# UCAGPS.net
KiCad netlist of a schematic drawn in Altium Designer
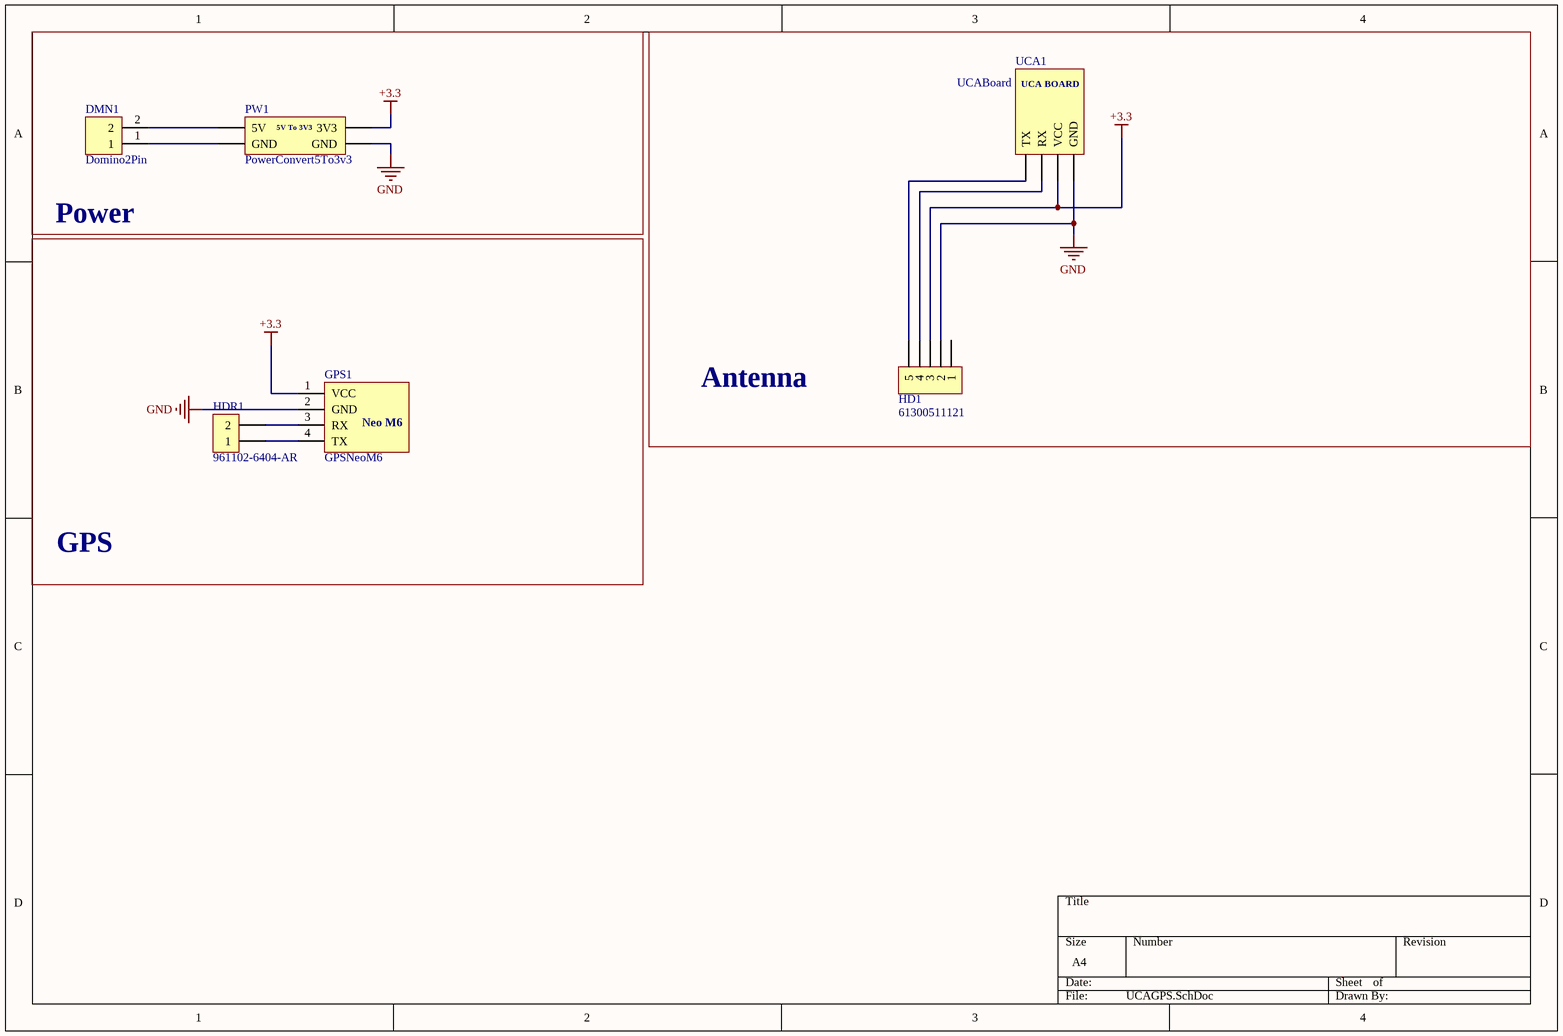
[diagram p0: UCAGPS.SchDoc]

(export (version "E")
  (design (tool "Eeschema 10.0.6"))
  (components
    (comp (ref "DMN1")
      (value "Domino2Pin")
      (footprint "CONN-SIL2")
      (libsource (lib "UCAGPS") (part "Domino2Pin"))
    )
    (comp (ref "GPS1") (value "GPSNeoM6") (footprint "GPSNEOM6") (libsource (lib "UCAGPS") (part "GPSNeoM6")))
    (comp (ref "HD1")
      (value "61300511121")
      (footprint "HEADER")
      (fields (field (name "MANUFACTURER") "Wurth Electronics"))
      (libsource (lib "UCAGPS") (part "61300511121"))
    )
    (comp (ref "HDR1")
      (value "961102-6404-AR")
      (footprint "header2pin")
      (description "CONN HEADER VERT SGL 2POS GOLD")
      (fields (field (name "MANUFACTURER") "3M"))
      (libsource (lib "UCAGPS") (part "961102-6404-AR"))
    )
    (comp (ref "PW1")
      (value "PowerConvert5To3v3")
      (footprint "PowerConvert5To3v3")
      (description "Convert 5 to 3.3")
      (libsource (lib "UCAGPS") (part "PowerConvert5To3v3"))
    )
    (comp (ref "UCA1") (value "UCABoard") (footprint "UCABOARD") (libsource (lib "UCAGPS") (part "UCABoard")))
  )
  (nets
    (net (code "1") (name "+3.3") (class "Default")
      (node (ref "GPS1") (pin "1") (pinfunction "VCC_1") (pintype "passive"))
      (node (ref "HD1") (pin "3") (pinfunction "3_3") (pintype "passive"))
      (node (ref "PW1") (pin "4") (pinfunction "3V3_4") (pintype "passive"))
      (node (ref "UCA1") (pin "3") (pinfunction "VCC_3") (pintype "passive"))
    )
    (net (code "2") (name "GND") (class "Default")
      (node (ref "GPS1") (pin "2") (pinfunction "GND_2") (pintype "passive"))
      (node (ref "HD1") (pin "2") (pinfunction "2_2") (pintype "passive"))
      (node (ref "PW1") (pin "3") (pinfunction "GND_3") (pintype "passive"))
      (node (ref "UCA1") (pin "4") (pinfunction "GND_4") (pintype "passive"))
    )
    (net (code "3") (name "Net-(DMN1-Pad1)") (class "Default")
      (node (ref "DMN1") (pin "1") (pinfunction "1_1") (pintype "passive"))
      (node (ref "PW1") (pin "2") (pinfunction "GND_2") (pintype "passive"))
    )
    (net (code "4") (name "Net-(GPS1-RX)") (class "Default")
      (node (ref "GPS1") (pin "3") (pinfunction "RX_3") (pintype "passive"))
      (node (ref "HDR1") (pin "2") (pinfunction "2_2") (pintype "passive"))
    )
    (net (code "5") (name "Net-(GPS1-TX)") (class "Default")
      (node (ref "GPS1") (pin "4") (pinfunction "TX_4") (pintype "passive"))
      (node (ref "HDR1") (pin "1") (pinfunction "1_1") (pintype "passive"))
    )
    (net (code "6") (name "Net-(PW1-5V)") (class "Default")
      (node (ref "DMN1") (pin "2") (pinfunction "2_2") (pintype "passive"))
      (node (ref "PW1") (pin "1") (pinfunction "5V_1") (pintype "passive"))
    )
    (net (code "7") (name "Net-(UCA1-RX)") (class "Default")
      (node (ref "HD1") (pin "4") (pinfunction "4_4") (pintype "passive"))
      (node (ref "UCA1") (pin "2") (pinfunction "RX_2") (pintype "passive"))
    )
    (net (code "8") (name "Net-(UCA1-TX)") (class "Default")
      (node (ref "HD1") (pin "5") (pinfunction "5_5") (pintype "passive"))
      (node (ref "UCA1") (pin "1") (pinfunction "TX_1") (pintype "passive"))
    )
    (net (code "9") (name "unconnected-(HD1-Pad1)") (class "Default")
      (node (ref "HD1") (pin "1") (pinfunction "1_1") (pintype "passive"))
    )
  )
)
